# dss_v3_up_DCDC.net
KiCad netlist of a schematic drawn in EAGLE
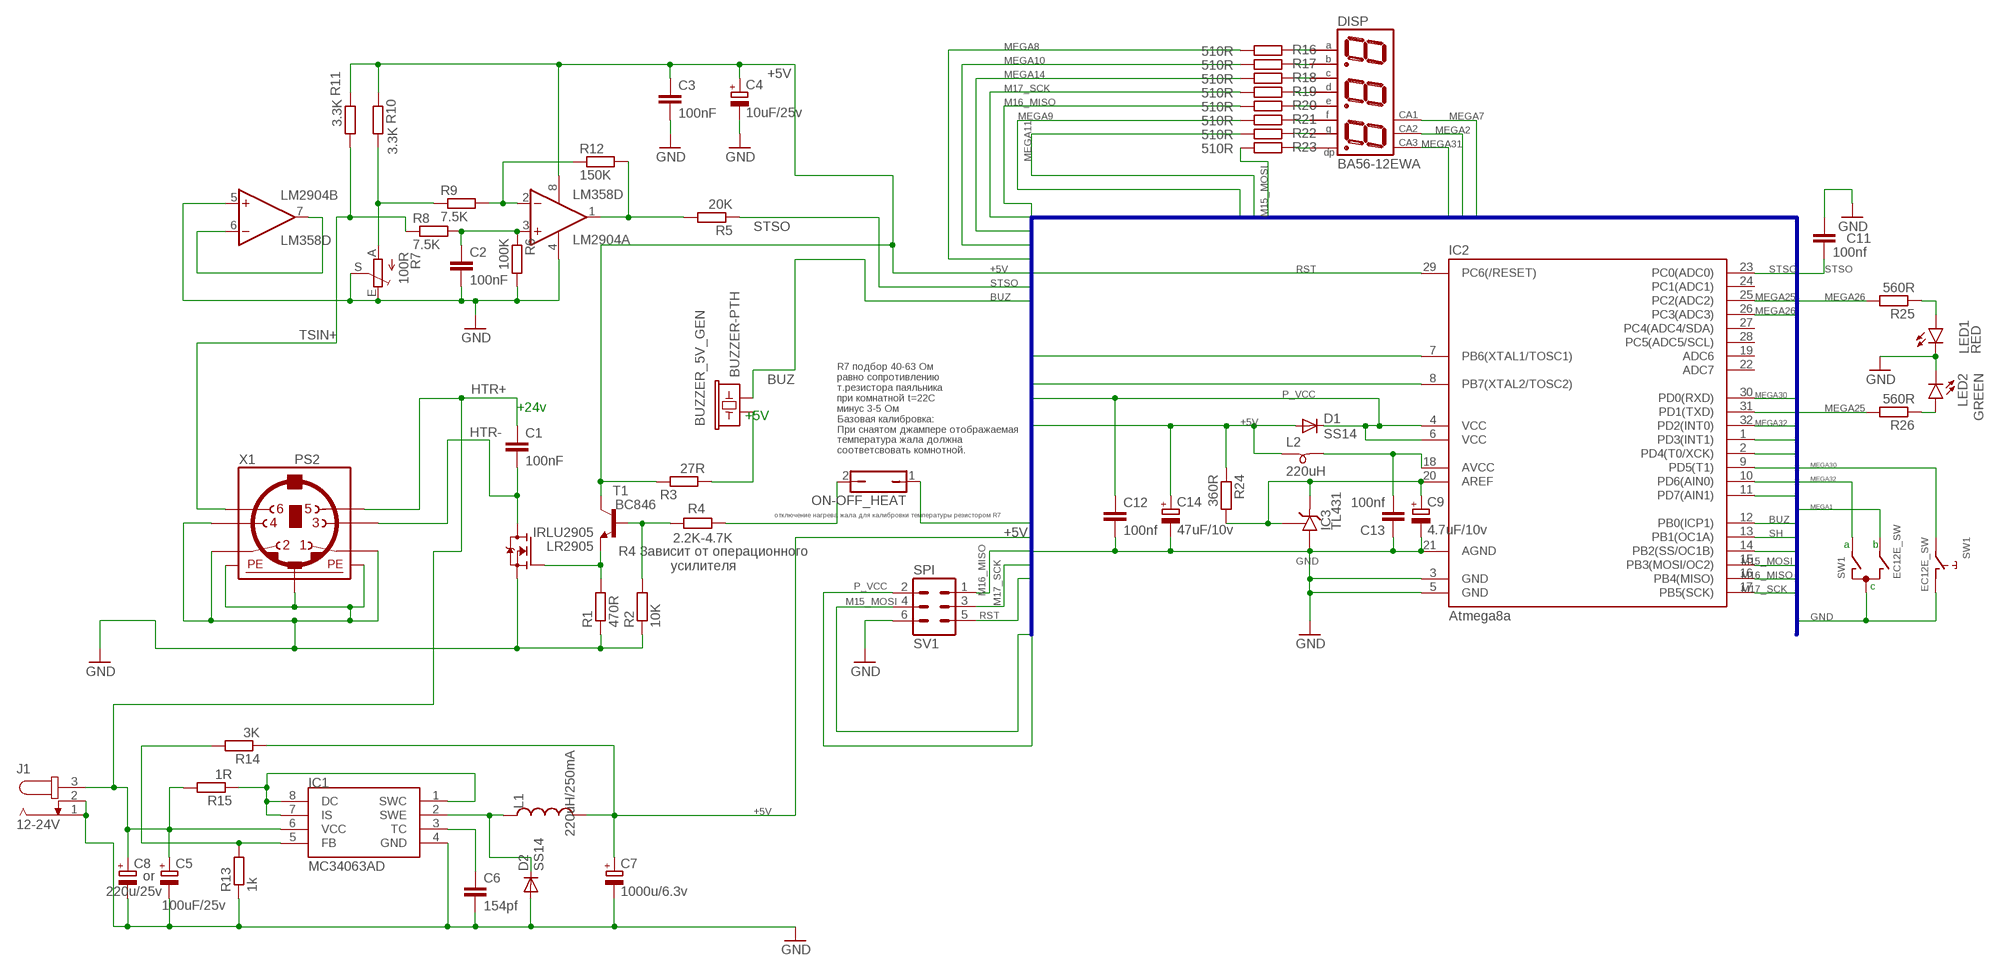
[diagram p0: schematic, sheet 1]

(export (version "E")
  (design (tool "Eeschema 10.0.6"))
  (components
    (comp (ref "BUZZER_5V_GEN")
      (value "BUZZER-PTH")
      (footprint "eagle-import:BUZZER-12MM")
      (libsource (lib "eagle-import") (part "BUZZER-PTH"))
    )
    (comp (ref "C1")
      (value "100nF")
      (footprint "eagle-import:C0805")
      (libsource (lib "eagle-import") (part "rcl_334_C-EUC0805"))
    )
    (comp (ref "C2")
      (value "100nF")
      (footprint "eagle-import:C0805")
      (libsource (lib "eagle-import") (part "C-EUC0805"))
    )
    (comp (ref "C3")
      (value "100nF")
      (footprint "eagle-import:C0805")
      (libsource (lib "eagle-import") (part "C-EUC0805"))
    )
    (comp (ref "C4")
      (value "10uF/25v")
      (footprint "eagle-import:CT3528")
      (libsource (lib "eagle-import") (part "CPOL-EUCT3528"))
    )
    (comp (ref "C5")
      (value "100uF/25v")
      (footprint "eagle-import:CT6032")
      (libsource (lib "eagle-import") (part "CPOL-EUCT6032"))
    )
    (comp (ref "C6")
      (value "154pf")
      (footprint "eagle-import:C0805")
      (libsource (lib "eagle-import") (part "C-EUC0805"))
    )
    (comp (ref "C7")
      (value "1000u/6.3v")
      (footprint "eagle-import:E3,5-8")
      (libsource (lib "eagle-import") (part "CPOL-EUE3.5-8"))
    )
    (comp (ref "C8")
      (value "220u/25v")
      (footprint "eagle-import:E3,5-8")
      (libsource (lib "eagle-import") (part "CPOL-EUE3.5-8"))
    )
    (comp (ref "C9")
      (value "4.7uF/10v")
      (footprint "eagle-import:CT3216")
      (libsource (lib "eagle-import") (part "CPOL-EUCT3216"))
    )
    (comp (ref "C11")
      (value "100nf")
      (footprint "eagle-import:C0805")
      (libsource (lib "eagle-import") (part "rcl_334_C-EUC0805"))
    )
    (comp (ref "C12")
      (value "100nf")
      (footprint "eagle-import:C0805")
      (libsource (lib "eagle-import") (part "rcl_334_C-EUC0805"))
    )
    (comp (ref "C13")
      (value "100nf")
      (footprint "eagle-import:C0805")
      (libsource (lib "eagle-import") (part "C-EUC0805"))
    )
    (comp (ref "C14")
      (value "47uF/10v")
      (footprint "eagle-import:CT3528")
      (libsource (lib "eagle-import") (part "CPOL-EUCT3528"))
    )
    (comp (ref "D1")
      (value "SS14")
      (footprint "eagle-import:DO214AC")
      (libsource (lib "eagle-import") (part "DIODE-DO214AC"))
    )
    (comp (ref "D2")
      (value "SS14")
      (footprint "eagle-import:DO214AC")
      (libsource (lib "eagle-import") (part "DIODE-DO214AC"))
    )
    (comp (ref "DISP")
      (value "BA56-12EWA")
      (footprint "eagle-import:BX56-12")
      (libsource (lib "eagle-import") (part "B?56-12WAAE"))
    )
    (comp (ref "IC1")
      (value "MC34063AD")
      (footprint "eagle-import:SOIC8")
      (libsource (lib "eagle-import") (part "MC34063AD"))
    )
    (comp (ref "IC2")
      (value "Atmega8a")
      (footprint "eagle-import:TQFP32-08")
      (libsource (lib "eagle-import") (part "ATMEGA8-AU"))
    )
    (comp (ref "IC3")
      (value "TL431")
      (footprint "eagle-import:SOT23")
      (libsource (lib "eagle-import") (part "TL431CLPSOT23"))
    )
    (comp (ref "IRLU2905")
      (value "LR2905")
      (footprint "eagle-import:TO252")
      (libsource (lib "eagle-import") (part "SPW47N60S5"))
    )
    (comp (ref "J1")
      (value "12-24V")
      (footprint "eagle-import:SPC4077")
      (libsource (lib "eagle-import") (part "JACK-PLUG0"))
    )
    (comp (ref "L1")
      (value "220uH/250mA")
      (footprint "eagle-import:L4532P")
      (libsource (lib "eagle-import") (part "L-USL4532P"))
    )
    (comp (ref "L2")
      (value "220uH")
      (footprint "eagle-import:SM-B5")
      (libsource (lib "eagle-import") (part "SM-B5"))
    )
    (comp (ref "LED1")
      (value "RED")
      (footprint "eagle-import:CHIP-LED0805")
      (libsource (lib "eagle-import") (part "LEDCHIP-LED0805"))
    )
    (comp (ref "LED2")
      (value "GREEN")
      (footprint "eagle-import:CHIP-LED0805")
      (libsource (lib "eagle-import") (part "LEDCHIP-LED0805"))
    )
    (comp (ref "LM2904")
      (value "LM358D")
      (footprint "eagle-import:SO08")
      (libsource (lib "eagle-import") (part "LM358D"))
    )
    (comp (ref "ON-OFF_HEAT")
      (value "JP1Q")
      (footprint "eagle-import:JP1")
      (libsource (lib "eagle-import") (part "JP1Q"))
    )
    (comp (ref "R1")
      (value "470R")
      (footprint "eagle-import:R0805")
      (libsource (lib "eagle-import") (part "rcl_334_R-EU_R0805"))
    )
    (comp (ref "R2")
      (value "10K")
      (footprint "eagle-import:R0805")
      (libsource (lib "eagle-import") (part "R-EU_R0805"))
    )
    (comp (ref "R3")
      (value "27R")
      (footprint "eagle-import:R0805")
      (libsource (lib "eagle-import") (part "R-EU_R0805"))
    )
    (comp (ref "R4")
      (value "2.2K-4.7K")
      (footprint "eagle-import:R0805")
      (libsource (lib "eagle-import") (part "R-EU_R0805"))
    )
    (comp (ref "R5")
      (value "20K")
      (footprint "eagle-import:R0805")
      (libsource (lib "eagle-import") (part "R-EU_R0805"))
    )
    (comp (ref "R6")
      (value "100K")
      (footprint "eagle-import:R0805")
      (libsource (lib "eagle-import") (part "R-EU_R0805"))
    )
    (comp (ref "R7")
      (value "100R")
      (footprint "eagle-import:B25P")
      (libsource (lib "eagle-import") (part "TRIM_EU-B25P"))
    )
    (comp (ref "R8")
      (value "7.5K")
      (footprint "eagle-import:R0805")
      (libsource (lib "eagle-import") (part "R-EU_R0805"))
    )
    (comp (ref "R9")
      (value "7.5K")
      (footprint "eagle-import:R0805")
      (libsource (lib "eagle-import") (part "R-EU_R0805"))
    )
    (comp (ref "R10")
      (value "3.3K")
      (footprint "eagle-import:R0805")
      (libsource (lib "eagle-import") (part "R-EU_R0805"))
    )
    (comp (ref "R11")
      (value "3.3K")
      (footprint "eagle-import:R0805")
      (libsource (lib "eagle-import") (part "R-EU_R0805"))
    )
    (comp (ref "R12")
      (value "150K")
      (footprint "eagle-import:R0805")
      (libsource (lib "eagle-import") (part "R-EU_R0805"))
    )
    (comp (ref "R13")
      (value "1k")
      (footprint "eagle-import:R0805")
      (libsource (lib "eagle-import") (part "R-EU_R0805"))
    )
    (comp (ref "R14")
      (value "3K")
      (footprint "eagle-import:R0805")
      (libsource (lib "eagle-import") (part "R-EU_R0805"))
    )
    (comp (ref "R15")
      (value "1R")
      (footprint "eagle-import:R0805")
      (libsource (lib "eagle-import") (part "R-EU_R0805"))
    )
    (comp (ref "R16")
      (value "510R")
      (footprint "eagle-import:R0805")
      (libsource (lib "eagle-import") (part "rcl_334_R-EU_R0805"))
    )
    (comp (ref "R17")
      (value "510R")
      (footprint "eagle-import:R0805")
      (libsource (lib "eagle-import") (part "rcl_334_R-EU_R0805"))
    )
    (comp (ref "R18")
      (value "510R")
      (footprint "eagle-import:R0805")
      (libsource (lib "eagle-import") (part "rcl_334_R-EU_R0805"))
    )
    (comp (ref "R19")
      (value "510R")
      (footprint "eagle-import:R0805")
      (libsource (lib "eagle-import") (part "rcl_334_R-EU_R0805"))
    )
    (comp (ref "R20")
      (value "510R")
      (footprint "eagle-import:R0805")
      (libsource (lib "eagle-import") (part "rcl_334_R-EU_R0805"))
    )
    (comp (ref "R21")
      (value "510R")
      (footprint "eagle-import:R0805")
      (libsource (lib "eagle-import") (part "rcl_334_R-EU_R0805"))
    )
    (comp (ref "R22")
      (value "510R")
      (footprint "eagle-import:R0805")
      (libsource (lib "eagle-import") (part "rcl_334_R-EU_R0805"))
    )
    (comp (ref "R23")
      (value "510R")
      (footprint "eagle-import:R0805")
      (libsource (lib "eagle-import") (part "rcl_334_R-EU_R0805"))
    )
    (comp (ref "R24")
      (value "360R")
      (footprint "eagle-import:R0805")
      (libsource (lib "eagle-import") (part "R-EU_R0805"))
    )
    (comp (ref "R25")
      (value "560R")
      (footprint "eagle-import:R0805")
      (libsource (lib "eagle-import") (part "rcl_334_R-EU_R0805"))
    )
    (comp (ref "R26")
      (value "560R")
      (footprint "eagle-import:R0805")
      (libsource (lib "eagle-import") (part "rcl_334_R-EU_R0805"))
    )
    (comp (ref "SV1")
      (value "SPI")
      (footprint "eagle-import:ML6")
      (libsource (lib "eagle-import") (part "ML6"))
    )
    (comp (ref "SW1")
      (value "EC12E_SW")
      (footprint "eagle-import:ALPS_EC12E_SW")
      (fields (field (name "MPN") "EC12E2424407"))
      (libsource (lib "eagle-import") (part "EC12E_SW"))
    )
    (comp (ref "T1")
      (value "BC846")
      (footprint "eagle-import:SOT23")
      (libsource (lib "eagle-import") (part "BC846"))
    )
    (comp (ref "X1")
      (value "PS2")
      (footprint "eagle-import:M_DIN6")
      (libsource (lib "eagle-import") (part "MINI_DIN_6"))
    )
  )
  (nets
    (net (code "1") (name "/+5V") (class "Default")
      (node (ref "C14") (pin "+") (pinfunction "+_+") (pintype "passive"))
      (node (ref "C3") (pin "1") (pinfunction "1_1") (pintype "passive"))
      (node (ref "C4") (pin "+") (pinfunction "+_+") (pintype "passive"))
      (node (ref "C7") (pin "+") (pinfunction "+_+") (pintype "passive"))
      (node (ref "D1") (pin "A") (pinfunction "A_A") (pintype "passive"))
      (node (ref "L1") (pin "2") (pinfunction "2_2") (pintype "passive"))
      (node (ref "L2") (pin "1") (pinfunction "1_1") (pintype "passive"))
      (node (ref "LM2904") (pin "8") (pinfunction "V+_8") (pintype "power_in"))
      (node (ref "R10") (pin "1") (pinfunction "1_1") (pintype "passive"))
      (node (ref "R11") (pin "1") (pinfunction "1_1") (pintype "passive"))
      (node (ref "R14") (pin "1") (pinfunction "1_1") (pintype "passive"))
      (node (ref "R24") (pin "1") (pinfunction "1_1") (pintype "passive"))
      (node (ref "R3") (pin "2") (pinfunction "2_2") (pintype "passive"))
      (node (ref "T1") (pin "3") (pinfunction "C_3") (pintype "passive"))
    )
    (net (code "2") (name "/BUZ") (class "Default")
      (node (ref "BUZZER_5V_GEN") (pin "-") (pinfunction "2_-") (pintype "passive"))
      (node (ref "IC2") (pin "12") (pinfunction "PB0(ICP1)_12") (pintype "bidirectional"))
    )
    (net (code "3") (name "/HTR+") (class "Default")
      (node (ref "C1") (pin "1") (pinfunction "1_1") (pintype "passive"))
      (node (ref "C5") (pin "+") (pinfunction "+_+") (pintype "passive"))
      (node (ref "C8") (pin "+") (pinfunction "+_+") (pintype "passive"))
      (node (ref "IC1") (pin "6") (pinfunction "VCC_6") (pintype "passive"))
      (node (ref "J1") (pin "3") (pinfunction "3_3") (pintype "passive"))
      (node (ref "R15") (pin "2") (pinfunction "2_2") (pintype "passive"))
      (node (ref "X1") (pin "6") (pinfunction "6_6") (pintype "passive"))
    )
    (net (code "4") (name "/HTR-") (class "Default")
      (node (ref "C1") (pin "2") (pinfunction "2_2") (pintype "passive"))
      (node (ref "IRLU2905") (pin "4") (pinfunction "D_4") (pintype "passive"))
      (node (ref "X1") (pin "3") (pinfunction "3_3") (pintype "passive"))
    )
    (net (code "5") (name "/M15_MOSI") (class "Default")
      (node (ref "IC2") (pin "15") (pinfunction "PB3(MOSI/OC2)_15") (pintype "bidirectional"))
      (node (ref "R23") (pin "2") (pinfunction "2_2") (pintype "passive"))
      (node (ref "SV1") (pin "4") (pinfunction "4_4") (pintype "passive"))
    )
    (net (code "6") (name "/M16_MISO") (class "Default")
      (node (ref "IC2") (pin "16") (pinfunction "PB4(MISO)_16") (pintype "bidirectional"))
      (node (ref "R20") (pin "2") (pinfunction "2_2") (pintype "passive"))
      (node (ref "SV1") (pin "1") (pinfunction "1_1") (pintype "passive"))
    )
    (net (code "7") (name "/M17_SCK") (class "Default")
      (node (ref "IC2") (pin "17") (pinfunction "PB5(SCK)_17") (pintype "bidirectional"))
      (node (ref "R19") (pin "2") (pinfunction "2_2") (pintype "passive"))
      (node (ref "SV1") (pin "3") (pinfunction "3_3") (pintype "passive"))
    )
    (net (code "8") (name "/MEGA1") (class "Default")
      (node (ref "IC2") (pin "1") (pinfunction "PD3(INT1)_1") (pintype "bidirectional"))
      (node (ref "SW1") (pin "B") (pinfunction "B_B") (pintype "passive"))
    )
    (net (code "9") (name "/MEGA2") (class "Default")
      (node (ref "DISP") (pin "9") (pinfunction "CA_9") (pintype "passive"))
      (node (ref "IC2") (pin "2") (pinfunction "PD4(T0/XCK)_2") (pintype "bidirectional"))
    )
    (net (code "10") (name "/MEGA7") (class "Default")
      (node (ref "DISP") (pin "12") (pinfunction "CA_12") (pintype "passive"))
      (node (ref "IC2") (pin "7") (pinfunction "PB6(XTAL1/TOSC1)_7") (pintype "bidirectional"))
    )
    (net (code "11") (name "/MEGA8") (class "Default")
      (node (ref "IC2") (pin "8") (pinfunction "PB7(XTAL2/TOSC2)_8") (pintype "bidirectional"))
      (node (ref "R16") (pin "2") (pinfunction "2_2") (pintype "passive"))
    )
    (net (code "12") (name "/MEGA9") (class "Default")
      (node (ref "IC2") (pin "9") (pinfunction "PD5(T1)_9") (pintype "bidirectional"))
      (node (ref "R21") (pin "2") (pinfunction "2_2") (pintype "passive"))
    )
    (net (code "13") (name "/MEGA10") (class "Default")
      (node (ref "IC2") (pin "10") (pinfunction "PD6(AIN0)_10") (pintype "bidirectional"))
      (node (ref "R17") (pin "2") (pinfunction "2_2") (pintype "passive"))
    )
    (net (code "14") (name "/MEGA11") (class "Default")
      (node (ref "IC2") (pin "11") (pinfunction "PD7(AIN1)_11") (pintype "bidirectional"))
      (node (ref "R22") (pin "2") (pinfunction "2_2") (pintype "passive"))
    )
    (net (code "15") (name "/MEGA14") (class "Default")
      (node (ref "IC2") (pin "14") (pinfunction "PB2(SS/OC1B)_14") (pintype "bidirectional"))
      (node (ref "R18") (pin "2") (pinfunction "2_2") (pintype "passive"))
    )
    (net (code "16") (name "/MEGA25") (class "Default")
      (node (ref "IC2") (pin "25") (pinfunction "PC2(ADC2)_25") (pintype "bidirectional"))
      (node (ref "R26") (pin "2") (pinfunction "2_2") (pintype "passive"))
    )
    (net (code "17") (name "/MEGA26") (class "Default")
      (node (ref "IC2") (pin "26") (pinfunction "PC3(ADC3)_26") (pintype "bidirectional"))
      (node (ref "R25") (pin "2") (pinfunction "2_2") (pintype "passive"))
    )
    (net (code "18") (name "/MEGA30") (class "Default")
      (node (ref "IC2") (pin "30") (pinfunction "PD0(RXD)_30") (pintype "bidirectional"))
      (node (ref "SW1") (pin "E") (pinfunction "2_E") (pintype "passive"))
    )
    (net (code "19") (name "/MEGA31") (class "Default")
      (node (ref "DISP") (pin "8") (pinfunction "CA_8") (pintype "passive"))
      (node (ref "IC2") (pin "31") (pinfunction "PD1(TXD)_31") (pintype "bidirectional"))
    )
    (net (code "20") (name "/MEGA32") (class "Default")
      (node (ref "IC2") (pin "32") (pinfunction "PD2(INT0)_32") (pintype "bidirectional"))
      (node (ref "SW1") (pin "A") (pinfunction "A_A") (pintype "passive"))
    )
    (net (code "21") (name "/P_VCC") (class "Default")
      (node (ref "C12") (pin "1") (pinfunction "1_1") (pintype "passive"))
      (node (ref "D1") (pin "C") (pinfunction "C_C") (pintype "passive"))
      (node (ref "IC2") (pin "4") (pinfunction "VCC_4") (pintype "power_in"))
      (node (ref "IC2") (pin "6") (pinfunction "VCC_6") (pintype "power_in"))
      (node (ref "SV1") (pin "2") (pinfunction "2_2") (pintype "passive"))
    )
    (net (code "22") (name "/RST") (class "Default")
      (node (ref "IC2") (pin "29") (pinfunction "PC6(/RESET)_29") (pintype "bidirectional"))
      (node (ref "SV1") (pin "5") (pinfunction "5_5") (pintype "passive"))
    )
    (net (code "23") (name "/SH") (class "Default")
      (node (ref "IC2") (pin "13") (pinfunction "PB1(OC1A)_13") (pintype "bidirectional"))
      (node (ref "ON-OFF_HEAT") (pin "1") (pinfunction "1_1") (pintype "passive"))
    )
    (net (code "24") (name "/STSO") (class "Default")
      (node (ref "C11") (pin "2") (pinfunction "2_2") (pintype "passive"))
      (node (ref "IC2") (pin "23") (pinfunction "PC0(ADC0)_23") (pintype "bidirectional"))
      (node (ref "R5") (pin "1") (pinfunction "1_1") (pintype "passive"))
    )
    (net (code "25") (name "/TSIN+") (class "Default")
      (node (ref "R11") (pin "2") (pinfunction "2_2") (pintype "passive"))
      (node (ref "R8") (pin "1") (pinfunction "1_1") (pintype "passive"))
      (node (ref "X1") (pin "8") (pinfunction "8_8") (pintype "passive"))
    )
    (net (code "26") (name "GND") (class "Default")
      (node (ref "C11") (pin "1") (pinfunction "1_1") (pintype "passive"))
      (node (ref "C12") (pin "2") (pinfunction "2_2") (pintype "passive"))
      (node (ref "C13") (pin "1") (pinfunction "1_1") (pintype "passive"))
      (node (ref "C14") (pin "-") (pinfunction "-_-") (pintype "passive"))
      (node (ref "C2") (pin "2") (pinfunction "2_2") (pintype "passive"))
      (node (ref "C3") (pin "2") (pinfunction "2_2") (pintype "passive"))
      (node (ref "C4") (pin "-") (pinfunction "-_-") (pintype "passive"))
      (node (ref "C5") (pin "-") (pinfunction "-_-") (pintype "passive"))
      (node (ref "C6") (pin "2") (pinfunction "2_2") (pintype "passive"))
      (node (ref "C7") (pin "-") (pinfunction "-_-") (pintype "passive"))
      (node (ref "C8") (pin "-") (pinfunction "-_-") (pintype "passive"))
      (node (ref "C9") (pin "-") (pinfunction "-_-") (pintype "passive"))
      (node (ref "D2") (pin "A") (pinfunction "A_A") (pintype "passive"))
      (node (ref "IC1") (pin "4") (pinfunction "GND_4") (pintype "passive"))
      (node (ref "IC2") (pin "21") (pinfunction "AGND_21") (pintype "power_in"))
      (node (ref "IC2") (pin "3") (pinfunction "GND_3") (pintype "power_in"))
      (node (ref "IC2") (pin "5") (pinfunction "GND_5") (pintype "power_in"))
      (node (ref "IC3") (pin "3") (pinfunction "A_3") (pintype "passive"))
      (node (ref "IRLU2905") (pin "3") (pinfunction "S_3") (pintype "passive"))
      (node (ref "J1") (pin "1") (pinfunction "1_1") (pintype "passive"))
      (node (ref "J1") (pin "2") (pinfunction "2_2") (pintype "passive"))
      (node (ref "LED1") (pin "C") (pinfunction "C_C") (pintype "passive"))
      (node (ref "LED2") (pin "C") (pinfunction "C_C") (pintype "passive"))
      (node (ref "LM2904") (pin "4") (pinfunction "V-_4") (pintype "power_in"))
      (node (ref "LM2904") (pin "5") (pinfunction "+IN_5") (pintype "input"))
      (node (ref "R1") (pin "1") (pinfunction "1_1") (pintype "passive"))
      (node (ref "R13") (pin "1") (pinfunction "1_1") (pintype "passive"))
      (node (ref "R2") (pin "1") (pinfunction "1_1") (pintype "passive"))
      (node (ref "R6") (pin "2") (pinfunction "2_2") (pintype "passive"))
      (node (ref "R7") (pin "E") (pinfunction "E_E") (pintype "passive"))
      (node (ref "R7") (pin "S") (pinfunction "S_S") (pintype "passive"))
      (node (ref "SV1") (pin "6") (pinfunction "6_6") (pintype "passive"))
      (node (ref "SW1") (pin "C") (pinfunction "C_C") (pintype "passive"))
      (node (ref "SW1") (pin "D") (pinfunction "1_D") (pintype "passive"))
      (node (ref "X1") (pin "1") (pinfunction "1_1") (pintype "passive"))
      (node (ref "X1") (pin "2") (pinfunction "2_2") (pintype "passive"))
      (node (ref "X1") (pin "5") (pinfunction "5_5") (pintype "passive"))
      (node (ref "X1") (pin "SH1") (pinfunction "PE1_SH1") (pintype "power_in"))
      (node (ref "X1") (pin "SH2") (pinfunction "PE2_SH2") (pintype "power_in"))
      (node (ref "X1") (pin "SH3") (pinfunction "PE3_SH3") (pintype "power_in"))
    )
    (net (code "27") (name "Net-(BUZZER_5V_GEN-1)") (class "Default")
      (node (ref "BUZZER_5V_GEN") (pin "+") (pinfunction "1_+") (pintype "passive"))
      (node (ref "R3") (pin "1") (pinfunction "1_1") (pintype "passive"))
    )
    (net (code "28") (name "Net-(DISP-A)") (class "Default")
      (node (ref "DISP") (pin "11") (pinfunction "A_11") (pintype "passive"))
      (node (ref "R16") (pin "1") (pinfunction "1_1") (pintype "passive"))
    )
    (net (code "29") (name "Net-(DISP-B)") (class "Default")
      (node (ref "DISP") (pin "7") (pinfunction "B_7") (pintype "passive"))
      (node (ref "R17") (pin "1") (pinfunction "1_1") (pintype "passive"))
    )
    (net (code "30") (name "Net-(DISP-C)") (class "Default")
      (node (ref "DISP") (pin "4") (pinfunction "C_4") (pintype "passive"))
      (node (ref "R18") (pin "1") (pinfunction "1_1") (pintype "passive"))
    )
    (net (code "31") (name "Net-(DISP-D)") (class "Default")
      (node (ref "DISP") (pin "2") (pinfunction "D_2") (pintype "passive"))
      (node (ref "R19") (pin "1") (pinfunction "1_1") (pintype "passive"))
    )
    (net (code "32") (name "Net-(DISP-DP)") (class "Default")
      (node (ref "DISP") (pin "3") (pinfunction "DP_3") (pintype "passive"))
      (node (ref "R23") (pin "1") (pinfunction "1_1") (pintype "passive"))
    )
    (net (code "33") (name "Net-(DISP-E)") (class "Default")
      (node (ref "DISP") (pin "1") (pinfunction "E_1") (pintype "passive"))
      (node (ref "R20") (pin "1") (pinfunction "1_1") (pintype "passive"))
    )
    (net (code "34") (name "Net-(DISP-F)") (class "Default")
      (node (ref "DISP") (pin "10") (pinfunction "F_10") (pintype "passive"))
      (node (ref "R21") (pin "1") (pinfunction "1_1") (pintype "passive"))
    )
    (net (code "35") (name "Net-(DISP-G)") (class "Default")
      (node (ref "DISP") (pin "5") (pinfunction "G_5") (pintype "passive"))
      (node (ref "R22") (pin "1") (pinfunction "1_1") (pintype "passive"))
    )
    (net (code "36") (name "Net-(IC1-DC)") (class "Default")
      (node (ref "IC1") (pin "1") (pinfunction "SWC_1") (pintype "passive"))
      (node (ref "IC1") (pin "7") (pinfunction "IS_7") (pintype "passive"))
      (node (ref "IC1") (pin "8") (pinfunction "DC_8") (pintype "passive"))
      (node (ref "R15") (pin "1") (pinfunction "1_1") (pintype "passive"))
    )
    (net (code "37") (name "Net-(IC1-FB)") (class "Default")
      (node (ref "IC1") (pin "5") (pinfunction "FB_5") (pintype "passive"))
      (node (ref "R13") (pin "2") (pinfunction "2_2") (pintype "passive"))
      (node (ref "R14") (pin "2") (pinfunction "2_2") (pintype "passive"))
    )
    (net (code "38") (name "Net-(IC1-SWE)") (class "Default")
      (node (ref "D2") (pin "C") (pinfunction "C_C") (pintype "passive"))
      (node (ref "IC1") (pin "2") (pinfunction "SWE_2") (pintype "passive"))
      (node (ref "L1") (pin "1") (pinfunction "1_1") (pintype "passive"))
    )
    (net (code "39") (name "Net-(IC1-TC)") (class "Default")
      (node (ref "C6") (pin "1") (pinfunction "1_1") (pintype "passive"))
      (node (ref "IC1") (pin "3") (pinfunction "TC_3") (pintype "passive"))
    )
    (net (code "40") (name "Net-(IC2-AREF)") (class "Default")
      (node (ref "C9") (pin "+") (pinfunction "+_+") (pintype "passive"))
      (node (ref "IC2") (pin "20") (pinfunction "AREF_20") (pintype "passive"))
      (node (ref "IC3") (pin "1") (pinfunction "C_1") (pintype "passive"))
      (node (ref "IC3") (pin "2") (pinfunction "R_2") (pintype "passive"))
      (node (ref "R24") (pin "2") (pinfunction "2_2") (pintype "passive"))
    )
    (net (code "41") (name "Net-(IC2-AVCC)") (class "Default")
      (node (ref "C13") (pin "2") (pinfunction "2_2") (pintype "passive"))
      (node (ref "IC2") (pin "18") (pinfunction "AVCC_18") (pintype "passive"))
      (node (ref "L2") (pin "2") (pinfunction "2_2") (pintype "passive"))
    )
    (net (code "42") (name "Net-(IRLU2905-G)") (class "Default")
      (node (ref "IRLU2905") (pin "1") (pinfunction "G_1") (pintype "passive"))
      (node (ref "R1") (pin "2") (pinfunction "2_2") (pintype "passive"))
      (node (ref "T1") (pin "2") (pinfunction "E_2") (pintype "passive"))
    )
    (net (code "43") (name "Net-(LED1-PadA)") (class "Default")
      (node (ref "LED1") (pin "A") (pinfunction "A_A") (pintype "passive"))
      (node (ref "R25") (pin "1") (pinfunction "1_1") (pintype "passive"))
    )
    (net (code "44") (name "Net-(LED2-PadA)") (class "Default")
      (node (ref "LED2") (pin "A") (pinfunction "A_A") (pintype "passive"))
      (node (ref "R26") (pin "1") (pinfunction "1_1") (pintype "passive"))
    )
    (net (code "45") (name "Net-(LM2904A-+IN)") (class "Default")
      (node (ref "C2") (pin "1") (pinfunction "1_1") (pintype "passive"))
      (node (ref "LM2904") (pin "3") (pinfunction "+IN_3") (pintype "input"))
      (node (ref "R6") (pin "1") (pinfunction "1_1") (pintype "passive"))
      (node (ref "R8") (pin "2") (pinfunction "2_2") (pintype "passive"))
    )
    (net (code "46") (name "Net-(LM2904A--IN)") (class "Default")
      (node (ref "LM2904") (pin "2") (pinfunction "-IN_2") (pintype "input"))
      (node (ref "R12") (pin "1") (pinfunction "1_1") (pintype "passive"))
      (node (ref "R9") (pin "2") (pinfunction "2_2") (pintype "passive"))
    )
    (net (code "47") (name "Net-(LM2904A-OUT)") (class "Default")
      (node (ref "LM2904") (pin "1") (pinfunction "OUT_1") (pintype "output"))
      (node (ref "R12") (pin "2") (pinfunction "2_2") (pintype "passive"))
      (node (ref "R5") (pin "2") (pinfunction "2_2") (pintype "passive"))
    )
    (net (code "48") (name "Net-(LM2904B--IN)") (class "Default")
      (node (ref "LM2904") (pin "6") (pinfunction "-IN_6") (pintype "input"))
      (node (ref "LM2904") (pin "7") (pinfunction "OUT_7") (pintype "output"))
    )
    (net (code "49") (name "Net-(ON-OFF_HEAT-Pad2)") (class "Default")
      (node (ref "ON-OFF_HEAT") (pin "2") (pinfunction "2_2") (pintype "passive"))
      (node (ref "R4") (pin "1") (pinfunction "1_1") (pintype "passive"))
    )
    (net (code "50") (name "Net-(R10-Pad2)") (class "Default")
      (node (ref "R10") (pin "2") (pinfunction "2_2") (pintype "passive"))
      (node (ref "R7") (pin "A") (pinfunction "A_A") (pintype "passive"))
      (node (ref "R9") (pin "1") (pinfunction "1_1") (pintype "passive"))
    )
    (net (code "51") (name "Net-(T1-B)") (class "Default")
      (node (ref "R2") (pin "2") (pinfunction "2_2") (pintype "passive"))
      (node (ref "R4") (pin "2") (pinfunction "2_2") (pintype "passive"))
      (node (ref "T1") (pin "1") (pinfunction "B_1") (pintype "passive"))
    )
    (net (code "52") (name "unconnected-(IC2-ADC6-Pad19)") (class "Default")
      (node (ref "IC2") (pin "19") (pinfunction "ADC6_19") (pintype "passive"))
    )
    (net (code "53") (name "unconnected-(IC2-ADC7-Pad22)") (class "Default")
      (node (ref "IC2") (pin "22") (pinfunction "ADC7_22") (pintype "passive"))
    )
    (net (code "54") (name "unconnected-(IC2-PC1(ADC1)-Pad24)") (class "Default")
      (node (ref "IC2") (pin "24") (pinfunction "PC1(ADC1)_24") (pintype "bidirectional"))
    )
    (net (code "55") (name "unconnected-(IC2-PC4(ADC4{slash}SDA)-Pad27)") (class "Default")
      (node (ref "IC2") (pin "27") (pinfunction "PC4(ADC4/SDA)_27") (pintype "bidirectional"))
    )
    (net (code "56") (name "unconnected-(IC2-PC5(ADC5{slash}SCL)-Pad28)") (class "Default")
      (node (ref "IC2") (pin "28") (pinfunction "PC5(ADC5/SCL)_28") (pintype "bidirectional"))
    )
  )
)
